# ShieldValvesSensor-v0.net
KiCad netlist of a schematic drawn in EAGLE
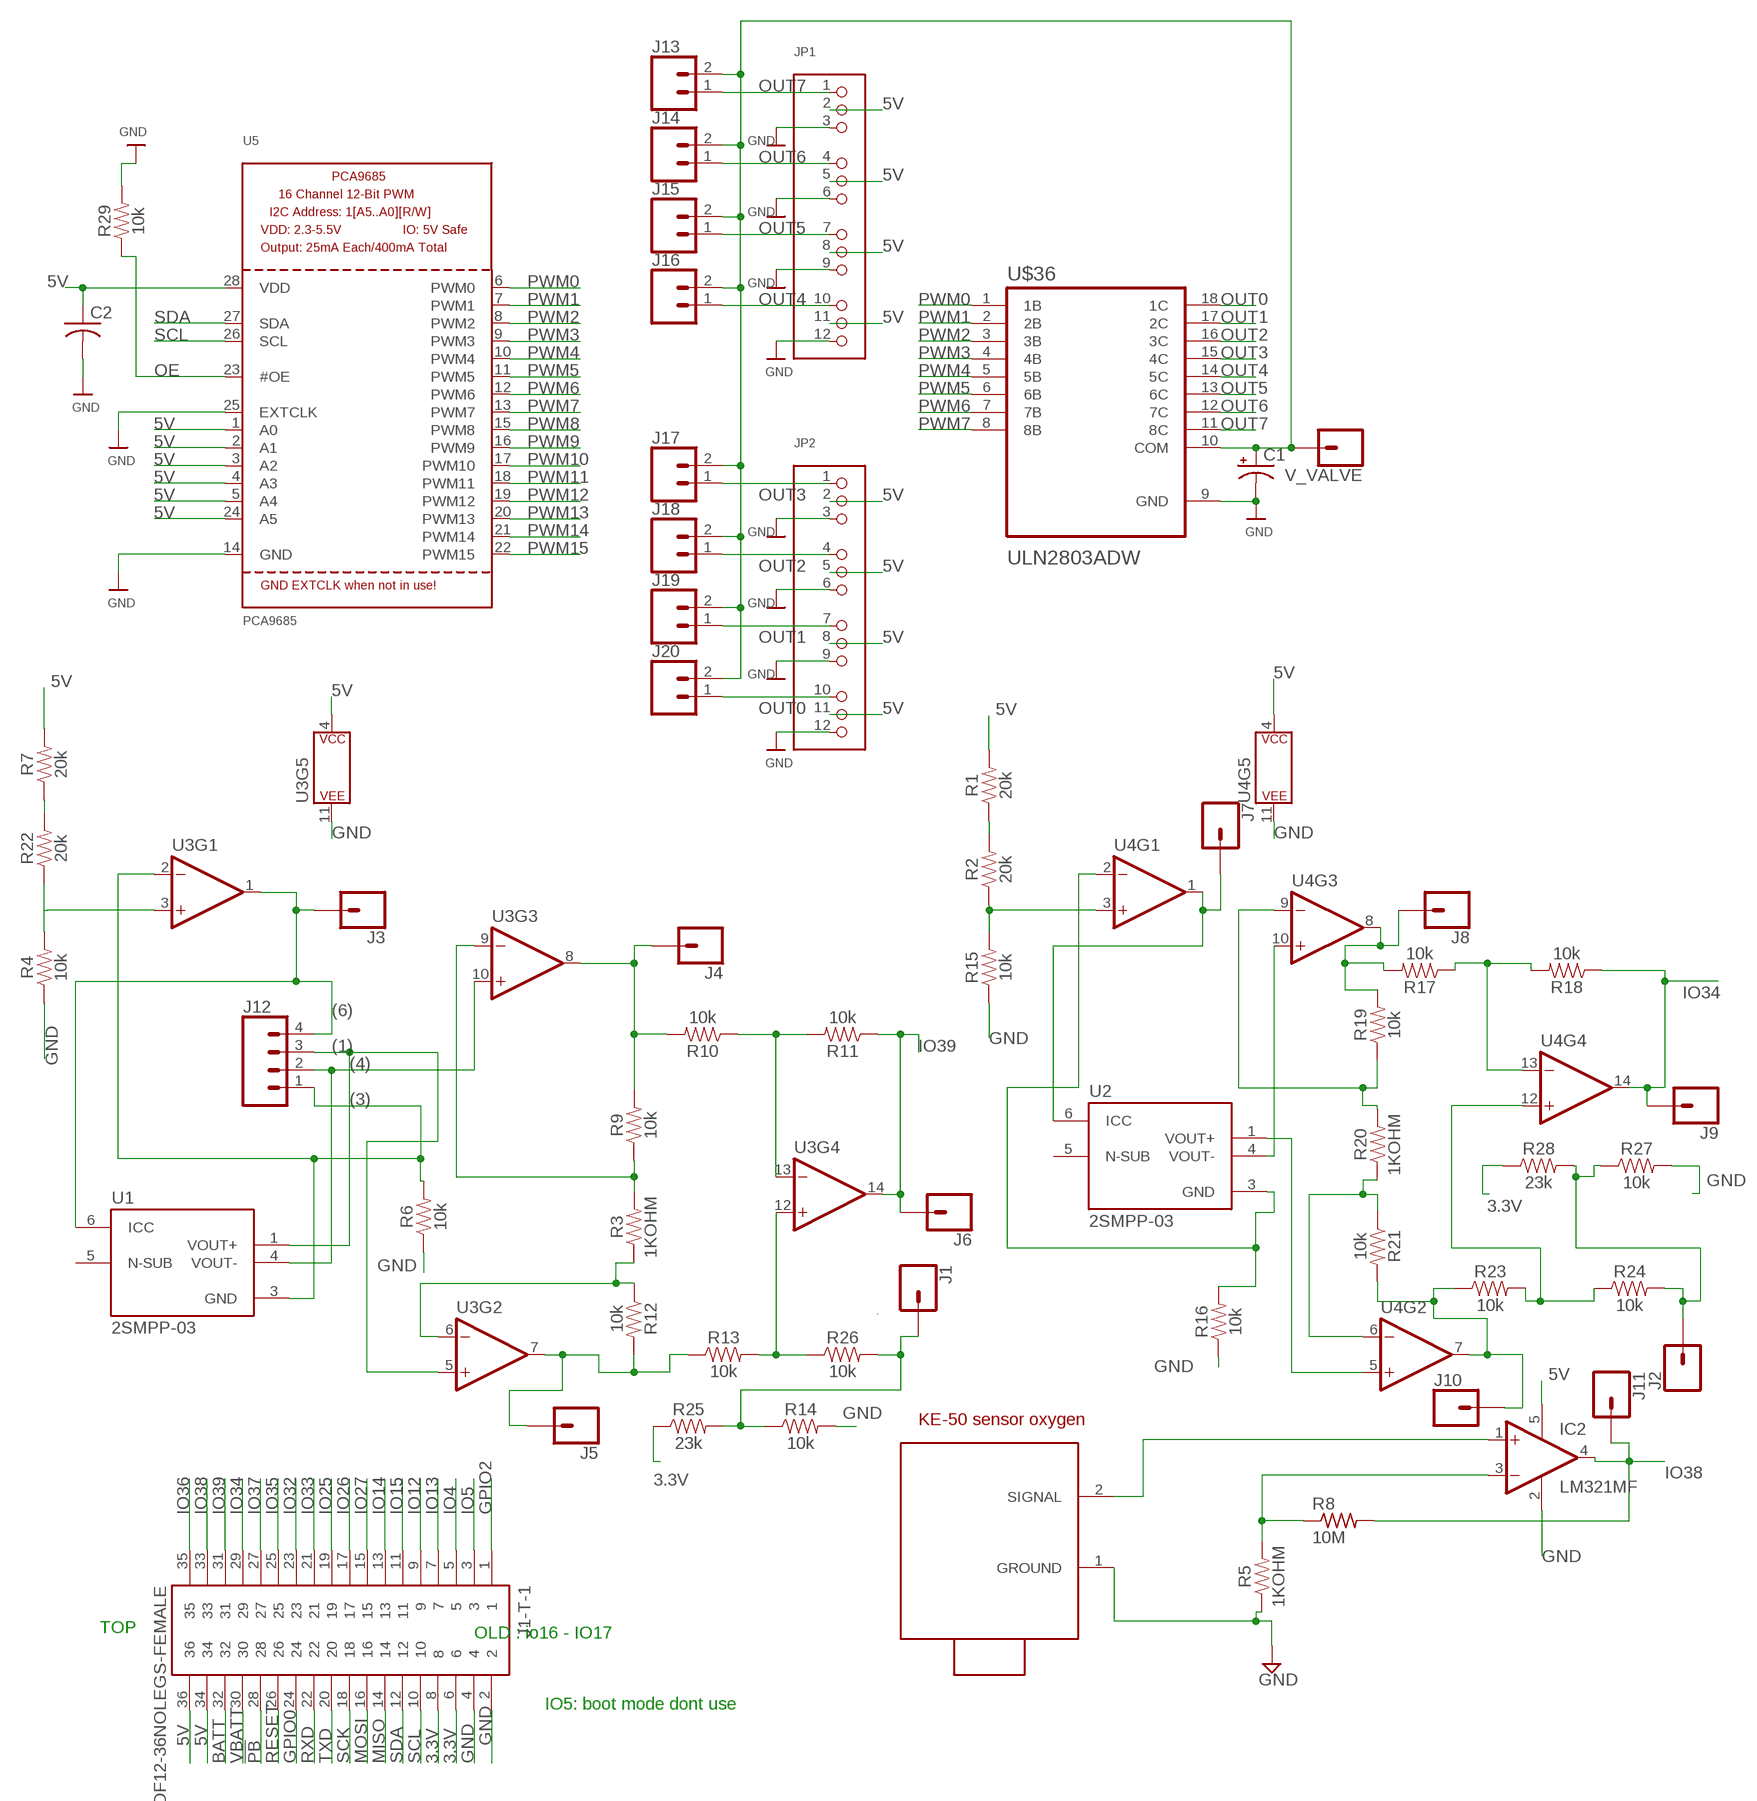
[diagram p0: schematic, sheet 1]

(export (version "E")
  (design (tool "Eeschema 10.0.6"))
  (components
    (comp (ref "C1")
      (value "CPOL-USE2-4")
      (footprint "eagle-import:E2-4")
      (libsource (lib "eagle-import") (part "CPOL-USE2-4"))
    )
    (comp (ref "C2")
      (value "C-USC0402")
      (footprint "eagle-import:C0402")
      (libsource (lib "eagle-import") (part "C-USC0402"))
    )
    (comp (ref "IC2")
      (value "LM321MF")
      (footprint "eagle-import:SOT23-5")
      (libsource (lib "eagle-import") (part "LM321?MF"))
    )
    (comp (ref "J1")
      (value "CONN_01")
      (footprint "eagle-import:1X01")
      (libsource (lib "eagle-import") (part "CONN_01"))
    )
    (comp (ref "J1-T-1")
      (value "DF12-36NOLEGS-FEMALE")
      (footprint "eagle-import:DF12-36-DP-NL")
      (libsource (lib "eagle-import") (part "DF12-36NOLEGS-FEMALE"))
    )
    (comp (ref "J2")
      (value "CONN_01")
      (footprint "eagle-import:1X01")
      (libsource (lib "eagle-import") (part "CONN_01"))
    )
    (comp (ref "J3")
      (value "CONN_01")
      (footprint "eagle-import:1X01")
      (libsource (lib "eagle-import") (part "CONN_01"))
    )
    (comp (ref "J4")
      (value "CONN_01")
      (footprint "eagle-import:1X01")
      (libsource (lib "eagle-import") (part "CONN_01"))
    )
    (comp (ref "J5")
      (value "CONN_01")
      (footprint "eagle-import:1X01")
      (libsource (lib "eagle-import") (part "CONN_01"))
    )
    (comp (ref "J6")
      (value "CONN_01")
      (footprint "eagle-import:1X01")
      (libsource (lib "eagle-import") (part "CONN_01"))
    )
    (comp (ref "J7")
      (value "CONN_01")
      (footprint "eagle-import:1X01")
      (libsource (lib "eagle-import") (part "CONN_01"))
    )
    (comp (ref "J8")
      (value "CONN_01")
      (footprint "eagle-import:1X01")
      (libsource (lib "eagle-import") (part "CONN_01"))
    )
    (comp (ref "J9")
      (value "CONN_01")
      (footprint "eagle-import:1X01")
      (libsource (lib "eagle-import") (part "CONN_01"))
    )
    (comp (ref "J10")
      (value "CONN_01")
      (footprint "eagle-import:1X01")
      (libsource (lib "eagle-import") (part "CONN_01"))
    )
    (comp (ref "J11")
      (value "CONN_01")
      (footprint "eagle-import:1X01")
      (libsource (lib "eagle-import") (part "CONN_01"))
    )
    (comp (ref "J12")
      (value "CONN_04PTH")
      (footprint "eagle-import:1X04")
      (libsource (lib "eagle-import") (part "CONN_04PTH"))
    )
    (comp (ref "J13")
      (value "CONN_02")
      (footprint "eagle-import:1X02")
      (libsource (lib "eagle-import") (part "CONN_02"))
    )
    (comp (ref "J14")
      (value "CONN_02")
      (footprint "eagle-import:1X02")
      (libsource (lib "eagle-import") (part "CONN_02"))
    )
    (comp (ref "J15")
      (value "CONN_02")
      (footprint "eagle-import:1X02")
      (libsource (lib "eagle-import") (part "CONN_02"))
    )
    (comp (ref "J16")
      (value "CONN_02")
      (footprint "eagle-import:1X02")
      (libsource (lib "eagle-import") (part "CONN_02"))
    )
    (comp (ref "J17")
      (value "CONN_02")
      (footprint "eagle-import:1X02")
      (libsource (lib "eagle-import") (part "CONN_02"))
    )
    (comp (ref "J18")
      (value "CONN_02")
      (footprint "eagle-import:1X02")
      (libsource (lib "eagle-import") (part "CONN_02"))
    )
    (comp (ref "J19")
      (value "CONN_02")
      (footprint "eagle-import:1X02")
      (libsource (lib "eagle-import") (part "CONN_02"))
    )
    (comp (ref "J20")
      (value "CONN_02")
      (footprint "eagle-import:1X02")
      (libsource (lib "eagle-import") (part "CONN_02"))
    )
    (comp (ref "JP1")
      (value "HEADER-3X04")
      (footprint "eagle-import:3X04")
      (libsource (lib "eagle-import") (part "HEADER-3X04"))
    )
    (comp (ref "JP2")
      (value "HEADER-3X04")
      (footprint "eagle-import:3X04")
      (libsource (lib "eagle-import") (part "HEADER-3X04"))
    )
    (comp (ref "R1")
      (value "20k")
      (footprint "eagle-import:0402-TIGHT")
      (libsource (lib "eagle-import") (part "20KOHM-0402T-1/16W-1%"))
    )
    (comp (ref "R2")
      (value "20k")
      (footprint "eagle-import:0402-TIGHT")
      (libsource (lib "eagle-import") (part "20KOHM-0402T-1/16W-1%"))
    )
    (comp (ref "R3")
      (value "1KOHM")
      (footprint "eagle-import:0402")
      (libsource (lib "eagle-import") (part "1KOHM-0402-1/16W-1%"))
    )
    (comp (ref "R4")
      (value "10k")
      (footprint "eagle-import:0402")
      (libsource (lib "eagle-import") (part "10KOHM-0402-1/16W-1%"))
    )
    (comp (ref "R5")
      (value "1KOHM")
      (footprint "eagle-import:0402")
      (libsource (lib "eagle-import") (part "1KOHM-0402-1/16W-1%"))
    )
    (comp (ref "R6")
      (value "10k")
      (footprint "eagle-import:0402")
      (libsource (lib "eagle-import") (part "10KOHM-0402-1/16W-1%"))
    )
    (comp (ref "R7")
      (value "20k")
      (footprint "eagle-import:0402-TIGHT")
      (libsource (lib "eagle-import") (part "20KOHM-0402T-1/16W-1%"))
    )
    (comp (ref "R8")
      (value "10M")
      (footprint "eagle-import:R0402")
      (libsource (lib "eagle-import") (part "R-US_R0402"))
    )
    (comp (ref "R9")
      (value "10k")
      (footprint "eagle-import:0402")
      (libsource (lib "eagle-import") (part "10KOHM-0402-1/16W-1%"))
    )
    (comp (ref "R10")
      (value "10k")
      (footprint "eagle-import:0402")
      (libsource (lib "eagle-import") (part "10KOHM-0402-1/16W-1%"))
    )
    (comp (ref "R11")
      (value "10k")
      (footprint "eagle-import:0402")
      (libsource (lib "eagle-import") (part "10KOHM-0402-1/16W-1%"))
    )
    (comp (ref "R12")
      (value "10k")
      (footprint "eagle-import:0402")
      (libsource (lib "eagle-import") (part "10KOHM-0402-1/16W-1%"))
    )
    (comp (ref "R13")
      (value "10k")
      (footprint "eagle-import:0402")
      (libsource (lib "eagle-import") (part "10KOHM-0402-1/16W-1%"))
    )
    (comp (ref "R14")
      (value "10k")
      (footprint "eagle-import:0402")
      (libsource (lib "eagle-import") (part "10KOHM-0402-1/16W-1%"))
    )
    (comp (ref "R15")
      (value "10k")
      (footprint "eagle-import:0402")
      (libsource (lib "eagle-import") (part "10KOHM-0402-1/16W-1%"))
    )
    (comp (ref "R16")
      (value "10k")
      (footprint "eagle-import:0402")
      (libsource (lib "eagle-import") (part "10KOHM-0402-1/16W-1%"))
    )
    (comp (ref "R17")
      (value "10k")
      (footprint "eagle-import:0402")
      (libsource (lib "eagle-import") (part "10KOHM-0402-1/16W-1%"))
    )
    (comp (ref "R18")
      (value "10k")
      (footprint "eagle-import:0402")
      (libsource (lib "eagle-import") (part "10KOHM-0402-1/16W-1%"))
    )
    (comp (ref "R19")
      (value "10k")
      (footprint "eagle-import:0402")
      (libsource (lib "eagle-import") (part "10KOHM-0402-1/16W-1%"))
    )
    (comp (ref "R20")
      (value "1KOHM")
      (footprint "eagle-import:0402")
      (libsource (lib "eagle-import") (part "1KOHM-0402-1/16W-1%"))
    )
    (comp (ref "R21")
      (value "10k")
      (footprint "eagle-import:0402")
      (libsource (lib "eagle-import") (part "10KOHM-0402-1/16W-1%"))
    )
    (comp (ref "R22")
      (value "20k")
      (footprint "eagle-import:0402-TIGHT")
      (libsource (lib "eagle-import") (part "20KOHM-0402T-1/16W-1%"))
    )
    (comp (ref "R23")
      (value "10k")
      (footprint "eagle-import:0402")
      (libsource (lib "eagle-import") (part "10KOHM-0402-1/16W-1%"))
    )
    (comp (ref "R24")
      (value "10k")
      (footprint "eagle-import:0402")
      (libsource (lib "eagle-import") (part "10KOHM-0402-1/16W-1%"))
    )
    (comp (ref "R25")
      (value "23k")
      (footprint "eagle-import:0402-TIGHT")
      (libsource (lib "eagle-import") (part "22KOHM-0402_TIGHT-1/10W-1%"))
    )
    (comp (ref "R26")
      (value "10k")
      (footprint "eagle-import:0402")
      (libsource (lib "eagle-import") (part "10KOHM-0402-1/16W-1%"))
    )
    (comp (ref "R27")
      (value "10k")
      (footprint "eagle-import:0402")
      (libsource (lib "eagle-import") (part "10KOHM-0402-1/16W-1%"))
    )
    (comp (ref "R28")
      (value "23k")
      (footprint "eagle-import:0402-TIGHT")
      (libsource (lib "eagle-import") (part "22KOHM-0402_TIGHT-1/10W-1%"))
    )
    (comp (ref "R29")
      (value "10k")
      (footprint "eagle-import:0402")
      (libsource (lib "eagle-import") (part "10KOHM-0402-1/16W-1%"))
    )
    (comp (ref "U$5")
      (value "KE-50")
      (footprint "eagle-import:KE")
      (libsource (lib "eagle-import") (part "KE-50"))
    )
    (comp (ref "U$36")
      (value "ULN2803ADW")
      (footprint "eagle-import:SOIC127P1030X265-18N")
      (libsource (lib "eagle-import") (part "ULN2803ADW"))
    )
    (comp (ref "U1")
      (value "2SMPP-03")
      (footprint "eagle-import:XDCR_2SMPP-03")
      (fields (field (name "MF") "Omron Electronics"))
      (libsource (lib "eagle-import") (part "2SMPP-03"))
    )
    (comp (ref "U2")
      (value "2SMPP-03")
      (footprint "eagle-import:XDCR_2SMPP-03")
      (fields (field (name "MF") "Omron Electronics"))
      (libsource (lib "eagle-import") (part "2SMPP-03"))
    )
    (comp (ref "U3")
      (value "LMV324SOP127P780X200-14N")
      (footprint "eagle-import:SOP127P780X200-14N")
      (libsource (lib "eagle-import") (part "LMV324SOP127P780X200-14N"))
    )
    (comp (ref "U4")
      (value "LMV324SOP127P780X200-14N")
      (footprint "eagle-import:SOP127P780X200-14N")
      (libsource (lib "eagle-import") (part "LMV324SOP127P780X200-14N"))
    )
    (comp (ref "U5")
      (value "PCA9685")
      (footprint "eagle-import:TSSOP28")
      (libsource (lib "eagle-import") (part "PCA9685"))
    )
    (comp (ref "V_VALVE")
      (value "CONN_01")
      (footprint "eagle-import:1X01")
      (libsource (lib "eagle-import") (part "SparkFun-Connectors_513_CONN_01"))
    )
  )
  (nets
    (net (code "1") (name "/(1)") (class "Default")
      (node (ref "J12") (pin "3") (pinfunction "3_3") (pintype "passive"))
      (node (ref "U1") (pin "1") (pinfunction "VOUT+_1") (pintype "output"))
      (node (ref "U3") (pin "5") (pinfunction "+IN_5") (pintype "input"))
    )
    (net (code "2") (name "/(3)") (class "Default")
      (node (ref "J12") (pin "1") (pinfunction "1_1") (pintype "passive"))
      (node (ref "R6") (pin "2") (pinfunction "2_2") (pintype "passive"))
      (node (ref "U1") (pin "3") (pinfunction "GND_3") (pintype "power_in"))
      (node (ref "U3") (pin "2") (pinfunction "-IN_2") (pintype "input"))
    )
    (net (code "3") (name "/(4)") (class "Default")
      (node (ref "J12") (pin "2") (pinfunction "2_2") (pintype "passive"))
      (node (ref "U1") (pin "4") (pinfunction "VOUT-_4") (pintype "output"))
      (node (ref "U3") (pin "10") (pinfunction "+IN_10") (pintype "input"))
    )
    (net (code "4") (name "/(6)") (class "Default")
      (node (ref "J12") (pin "4") (pinfunction "4_4") (pintype "passive"))
      (node (ref "J3") (pin "1") (pinfunction "1_1") (pintype "passive"))
      (node (ref "U1") (pin "6") (pinfunction "ICC_6") (pintype "input"))
      (node (ref "U3") (pin "1") (pinfunction "OUT_1") (pintype "output"))
    )
    (net (code "5") (name "/3.3V") (class "Default")
      (node (ref "J1-T-1") (pin "6") (pinfunction "6_6") (pintype "bidirectional"))
      (node (ref "J1-T-1") (pin "8") (pinfunction "8_8") (pintype "bidirectional"))
      (node (ref "R25") (pin "1") (pinfunction "1_1") (pintype "passive"))
      (node (ref "R28") (pin "1") (pinfunction "1_1") (pintype "passive"))
    )
    (net (code "6") (name "/5V") (class "Default")
      (node (ref "C2") (pin "1") (pinfunction "1_1") (pintype "passive"))
      (node (ref "IC2") (pin "5") (pinfunction "V+_5") (pintype "power_in"))
      (node (ref "J1-T-1") (pin "34") (pinfunction "34_34") (pintype "bidirectional"))
      (node (ref "J1-T-1") (pin "36") (pinfunction "36_36") (pintype "bidirectional"))
      (node (ref "JP1") (pin "11") (pinfunction "11_11") (pintype "passive"))
      (node (ref "JP1") (pin "2") (pinfunction "2_2") (pintype "passive"))
      (node (ref "JP1") (pin "5") (pinfunction "5_5") (pintype "passive"))
      (node (ref "JP1") (pin "8") (pinfunction "8_8") (pintype "passive"))
      (node (ref "JP2") (pin "11") (pinfunction "11_11") (pintype "passive"))
      (node (ref "JP2") (pin "2") (pinfunction "2_2") (pintype "passive"))
      (node (ref "JP2") (pin "5") (pinfunction "5_5") (pintype "passive"))
      (node (ref "JP2") (pin "8") (pinfunction "8_8") (pintype "passive"))
      (node (ref "R1") (pin "2") (pinfunction "2_2") (pintype "passive"))
      (node (ref "R7") (pin "2") (pinfunction "2_2") (pintype "passive"))
      (node (ref "U3") (pin "4") (pinfunction "P$V+_4") (pintype "bidirectional"))
      (node (ref "U4") (pin "4") (pinfunction "P$V+_4") (pintype "bidirectional"))
      (node (ref "U5") (pin "1") (pinfunction "A0_1") (pintype "bidirectional"))
      (node (ref "U5") (pin "2") (pinfunction "A1_2") (pintype "bidirectional"))
      (node (ref "U5") (pin "24") (pinfunction "A5_24") (pintype "bidirectional"))
      (node (ref "U5") (pin "28") (pinfunction "VDD_28") (pintype "power_in"))
      (node (ref "U5") (pin "3") (pinfunction "A2_3") (pintype "bidirectional"))
      (node (ref "U5") (pin "4") (pinfunction "A3_4") (pintype "bidirectional"))
      (node (ref "U5") (pin "5") (pinfunction "A4_5") (pintype "bidirectional"))
    )
    (net (code "7") (name "/BATT") (class "Default")
      (node (ref "J1-T-1") (pin "32") (pinfunction "32_32") (pintype "bidirectional"))
    )
    (net (code "8") (name "/GPIO0") (class "Default")
      (node (ref "J1-T-1") (pin "24") (pinfunction "24_24") (pintype "bidirectional"))
    )
    (net (code "9") (name "/GPIO2") (class "Default")
      (node (ref "J1-T-1") (pin "1") (pinfunction "1_1") (pintype "bidirectional"))
    )
    (net (code "10") (name "/IO4") (class "Default")
      (node (ref "J1-T-1") (pin "5") (pinfunction "5_5") (pintype "bidirectional"))
    )
    (net (code "11") (name "/IO5") (class "Default")
      (node (ref "J1-T-1") (pin "3") (pinfunction "3_3") (pintype "bidirectional"))
    )
    (net (code "12") (name "/IO12") (class "Default")
      (node (ref "J1-T-1") (pin "9") (pinfunction "9_9") (pintype "bidirectional"))
    )
    (net (code "13") (name "/IO13") (class "Default")
      (node (ref "J1-T-1") (pin "7") (pinfunction "7_7") (pintype "bidirectional"))
    )
    (net (code "14") (name "/IO14") (class "Default")
      (node (ref "J1-T-1") (pin "13") (pinfunction "13_13") (pintype "bidirectional"))
    )
    (net (code "15") (name "/IO15") (class "Default")
      (node (ref "J1-T-1") (pin "11") (pinfunction "11_11") (pintype "bidirectional"))
    )
    (net (code "16") (name "/IO25") (class "Default")
      (node (ref "J1-T-1") (pin "19") (pinfunction "19_19") (pintype "bidirectional"))
    )
    (net (code "17") (name "/IO26") (class "Default")
      (node (ref "J1-T-1") (pin "17") (pinfunction "17_17") (pintype "bidirectional"))
    )
    (net (code "18") (name "/IO27") (class "Default")
      (node (ref "J1-T-1") (pin "15") (pinfunction "15_15") (pintype "bidirectional"))
    )
    (net (code "19") (name "/IO32") (class "Default")
      (node (ref "J1-T-1") (pin "23") (pinfunction "23_23") (pintype "bidirectional"))
    )
    (net (code "20") (name "/IO33") (class "Default")
      (node (ref "J1-T-1") (pin "21") (pinfunction "21_21") (pintype "bidirectional"))
    )
    (net (code "21") (name "/IO34") (class "Default")
      (node (ref "J1-T-1") (pin "29") (pinfunction "29_29") (pintype "bidirectional"))
      (node (ref "J9") (pin "1") (pinfunction "1_1") (pintype "passive"))
      (node (ref "R18") (pin "1") (pinfunction "1_1") (pintype "passive"))
      (node (ref "U4") (pin "14") (pinfunction "OUT_14") (pintype "output"))
    )
    (net (code "22") (name "/IO35") (class "Default")
      (node (ref "J1-T-1") (pin "25") (pinfunction "25_25") (pintype "bidirectional"))
    )
    (net (code "23") (name "/IO36") (class "Default")
      (node (ref "J1-T-1") (pin "35") (pinfunction "35_35") (pintype "bidirectional"))
    )
    (net (code "24") (name "/IO37") (class "Default")
      (node (ref "J1-T-1") (pin "27") (pinfunction "27_27") (pintype "bidirectional"))
    )
    (net (code "25") (name "/IO38") (class "Default")
      (node (ref "IC2") (pin "4") (pinfunction "OUT_4") (pintype "output"))
      (node (ref "J1-T-1") (pin "33") (pinfunction "33_33") (pintype "bidirectional"))
      (node (ref "J11") (pin "1") (pinfunction "1_1") (pintype "passive"))
      (node (ref "R8") (pin "2") (pinfunction "2_2") (pintype "passive"))
    )
    (net (code "26") (name "/IO39") (class "Default")
      (node (ref "J1-T-1") (pin "31") (pinfunction "31_31") (pintype "bidirectional"))
      (node (ref "J6") (pin "1") (pinfunction "1_1") (pintype "passive"))
      (node (ref "R11") (pin "1") (pinfunction "1_1") (pintype "passive"))
      (node (ref "U3") (pin "14") (pinfunction "OUT_14") (pintype "output"))
    )
    (net (code "27") (name "/MISO") (class "Default")
      (node (ref "J1-T-1") (pin "14") (pinfunction "14_14") (pintype "bidirectional"))
    )
    (net (code "28") (name "/MOSI") (class "Default")
      (node (ref "J1-T-1") (pin "16") (pinfunction "16_16") (pintype "bidirectional"))
    )
    (net (code "29") (name "/OE") (class "Default")
      (node (ref "R29") (pin "1") (pinfunction "1_1") (pintype "passive"))
      (node (ref "U5") (pin "23") (pinfunction "#OE_23") (pintype "input"))
    )
    (net (code "30") (name "/OUT0") (class "Default")
      (node (ref "J20") (pin "1") (pinfunction "1_1") (pintype "passive"))
      (node (ref "JP2") (pin "10") (pinfunction "10_10") (pintype "passive"))
      (node (ref "U$36") (pin "18") (pinfunction "1C_18") (pintype "output"))
    )
    (net (code "31") (name "/OUT1") (class "Default")
      (node (ref "J19") (pin "1") (pinfunction "1_1") (pintype "passive"))
      (node (ref "JP2") (pin "7") (pinfunction "7_7") (pintype "passive"))
      (node (ref "U$36") (pin "17") (pinfunction "2C_17") (pintype "output"))
    )
    (net (code "32") (name "/OUT2") (class "Default")
      (node (ref "J18") (pin "1") (pinfunction "1_1") (pintype "passive"))
      (node (ref "JP2") (pin "4") (pinfunction "4_4") (pintype "passive"))
      (node (ref "U$36") (pin "16") (pinfunction "3C_16") (pintype "output"))
    )
    (net (code "33") (name "/OUT3") (class "Default")
      (node (ref "J17") (pin "1") (pinfunction "1_1") (pintype "passive"))
      (node (ref "JP2") (pin "1") (pinfunction "1_1") (pintype "passive"))
      (node (ref "U$36") (pin "15") (pinfunction "4C_15") (pintype "output"))
    )
    (net (code "34") (name "/OUT4") (class "Default")
      (node (ref "J16") (pin "1") (pinfunction "1_1") (pintype "passive"))
      (node (ref "JP1") (pin "10") (pinfunction "10_10") (pintype "passive"))
      (node (ref "U$36") (pin "14") (pinfunction "5C_14") (pintype "output"))
    )
    (net (code "35") (name "/OUT5") (class "Default")
      (node (ref "J15") (pin "1") (pinfunction "1_1") (pintype "passive"))
      (node (ref "JP1") (pin "7") (pinfunction "7_7") (pintype "passive"))
      (node (ref "U$36") (pin "13") (pinfunction "6C_13") (pintype "output"))
    )
    (net (code "36") (name "/OUT6") (class "Default")
      (node (ref "J14") (pin "1") (pinfunction "1_1") (pintype "passive"))
      (node (ref "JP1") (pin "4") (pinfunction "4_4") (pintype "passive"))
      (node (ref "U$36") (pin "12") (pinfunction "7C_12") (pintype "output"))
    )
    (net (code "37") (name "/OUT7") (class "Default")
      (node (ref "J13") (pin "1") (pinfunction "1_1") (pintype "passive"))
      (node (ref "JP1") (pin "1") (pinfunction "1_1") (pintype "passive"))
      (node (ref "U$36") (pin "11") (pinfunction "8C_11") (pintype "output"))
    )
    (net (code "38") (name "/PWM0") (class "Default")
      (node (ref "U$36") (pin "1") (pinfunction "1B_1") (pintype "input"))
      (node (ref "U5") (pin "6") (pinfunction "PWM0_6") (pintype "output"))
    )
    (net (code "39") (name "/PWM1") (class "Default")
      (node (ref "U$36") (pin "2") (pinfunction "2B_2") (pintype "input"))
      (node (ref "U5") (pin "7") (pinfunction "PWM1_7") (pintype "output"))
    )
    (net (code "40") (name "/PWM2") (class "Default")
      (node (ref "U$36") (pin "3") (pinfunction "3B_3") (pintype "input"))
      (node (ref "U5") (pin "8") (pinfunction "PWM2_8") (pintype "output"))
    )
    (net (code "41") (name "/PWM3") (class "Default")
      (node (ref "U$36") (pin "4") (pinfunction "4B_4") (pintype "input"))
      (node (ref "U5") (pin "9") (pinfunction "PWM3_9") (pintype "output"))
    )
    (net (code "42") (name "/PWM4") (class "Default")
      (node (ref "U$36") (pin "5") (pinfunction "5B_5") (pintype "input"))
      (node (ref "U5") (pin "10") (pinfunction "PWM4_10") (pintype "output"))
    )
    (net (code "43") (name "/PWM5") (class "Default")
      (node (ref "U$36") (pin "6") (pinfunction "6B_6") (pintype "input"))
      (node (ref "U5") (pin "11") (pinfunction "PWM5_11") (pintype "output"))
    )
    (net (code "44") (name "/PWM6") (class "Default")
      (node (ref "U$36") (pin "7") (pinfunction "7B_7") (pintype "input"))
      (node (ref "U5") (pin "12") (pinfunction "PWM6_12") (pintype "output"))
    )
    (net (code "45") (name "/PWM7") (class "Default")
      (node (ref "U$36") (pin "8") (pinfunction "8B_8") (pintype "input"))
      (node (ref "U5") (pin "13") (pinfunction "PWM7_13") (pintype "output"))
    )
    (net (code "46") (name "/PWM8") (class "Default")
      (node (ref "U5") (pin "15") (pinfunction "PWM8_15") (pintype "output"))
    )
    (net (code "47") (name "/PWM9") (class "Default")
      (node (ref "U5") (pin "16") (pinfunction "PWM9_16") (pintype "output"))
    )
    (net (code "48") (name "/PWM10") (class "Default")
      (node (ref "U5") (pin "17") (pinfunction "PWM10_17") (pintype "output"))
    )
    (net (code "49") (name "/PWM11") (class "Default")
      (node (ref "U5") (pin "18") (pinfunction "PWM11_18") (pintype "output"))
    )
    (net (code "50") (name "/PWM12") (class "Default")
      (node (ref "U5") (pin "19") (pinfunction "PWM12_19") (pintype "output"))
    )
    (net (code "51") (name "/PWM13") (class "Default")
      (node (ref "U5") (pin "20") (pinfunction "PWM13_20") (pintype "output"))
    )
    (net (code "52") (name "/PWM14") (class "Default")
      (node (ref "U5") (pin "21") (pinfunction "PWM14_21") (pintype "output"))
    )
    (net (code "53") (name "/PWM15") (class "Default")
      (node (ref "U5") (pin "22") (pinfunction "PWM15_22") (pintype "output"))
    )
    (net (code "54") (name "/RESET") (class "Default")
      (node (ref "J1-T-1") (pin "26") (pinfunction "26_26") (pintype "bidirectional"))
    )
    (net (code "55") (name "/RXD") (class "Default")
      (node (ref "J1-T-1") (pin "22") (pinfunction "22_22") (pintype "bidirectional"))
    )
    (net (code "56") (name "/SCK") (class "Default")
      (node (ref "J1-T-1") (pin "18") (pinfunction "18_18") (pintype "bidirectional"))
    )
    (net (code "57") (name "/SCL") (class "Default")
      (node (ref "J1-T-1") (pin "10") (pinfunction "10_10") (pintype "bidirectional"))
      (node (ref "U5") (pin "26") (pinfunction "SCL_26") (pintype "bidirectional"))
    )
    (net (code "58") (name "/SDA") (class "Default")
      (node (ref "J1-T-1") (pin "12") (pinfunction "12_12") (pintype "bidirectional"))
      (node (ref "U5") (pin "27") (pinfunction "SDA_27") (pintype "bidirectional"))
    )
    (net (code "59") (name "/TXD") (class "Default")
      (node (ref "J1-T-1") (pin "20") (pinfunction "20_20") (pintype "bidirectional"))
    )
    (net (code "60") (name "/VBATT") (class "Default")
      (node (ref "J1-T-1") (pin "30") (pinfunction "30_30") (pintype "bidirectional"))
    )
    (net (code "61") (name "/~{PB}") (class "Default")
      (node (ref "J1-T-1") (pin "28") (pinfunction "28_28") (pintype "bidirectional"))
    )
    (net (code "62") (name "GND") (class "Default")
      (node (ref "C1") (pin "-") (pinfunction "-_-") (pintype "passive"))
      (node (ref "C2") (pin "2") (pinfunction "2_2") (pintype "passive"))
      (node (ref "IC2") (pin "2") (pinfunction "V-_2") (pintype "power_in"))
      (node (ref "J1-T-1") (pin "2") (pinfunction "2_2") (pintype "bidirectional"))
      (node (ref "J1-T-1") (pin "4") (pinfunction "4_4") (pintype "bidirectional"))
      (node (ref "JP1") (pin "12") (pinfunction "12_12") (pintype "passive"))
      (node (ref "JP1") (pin "3") (pinfunction "3_3") (pintype "passive"))
      (node (ref "JP1") (pin "6") (pinfunction "6_6") (pintype "passive"))
      (node (ref "JP1") (pin "9") (pinfunction "9_9") (pintype "passive"))
      (node (ref "JP2") (pin "12") (pinfunction "12_12") (pintype "passive"))
      (node (ref "JP2") (pin "3") (pinfunction "3_3") (pintype "passive"))
      (node (ref "JP2") (pin "6") (pinfunction "6_6") (pintype "passive"))
      (node (ref "JP2") (pin "9") (pinfunction "9_9") (pintype "passive"))
      (node (ref "R14") (pin "2") (pinfunction "2_2") (pintype "passive"))
      (node (ref "R15") (pin "1") (pinfunction "1_1") (pintype "passive"))
      (node (ref "R16") (pin "1") (pinfunction "1_1") (pintype "passive"))
      (node (ref "R27") (pin "2") (pinfunction "2_2") (pintype "passive"))
      (node (ref "R29") (pin "2") (pinfunction "2_2") (pintype "passive"))
      (node (ref "R4") (pin "1") (pinfunction "1_1") (pintype "passive"))
      (node (ref "R5") (pin "1") (pinfunction "1_1") (pintype "passive"))
      (node (ref "R6") (pin "1") (pinfunction "1_1") (pintype "passive"))
      (node (ref "U$36") (pin "9") (pinfunction "GND_9") (pintype "power_in"))
      (node (ref "U$5") (pin "1") (pinfunction "GROUND_1") (pintype "bidirectional"))
      (node (ref "U3") (pin "11") (pinfunction "P$V-_11") (pintype "bidirectional"))
      (node (ref "U4") (pin "11") (pinfunction "P$V-_11") (pintype "bidirectional"))
      (node (ref "U5") (pin "14") (pinfunction "GND_14") (pintype "power_in"))
      (node (ref "U5") (pin "25") (pinfunction "EXTCLK_25") (pintype "input"))
    )
    (net (code "63") (name "Net-(IC2-+IN)") (class "Default")
      (node (ref "IC2") (pin "1") (pinfunction "+IN_1") (pintype "input"))
      (node (ref "U$5") (pin "2") (pinfunction "SIGNAL_2") (pintype "bidirectional"))
    )
    (net (code "64") (name "Net-(IC2--IN)") (class "Default")
      (node (ref "IC2") (pin "3") (pinfunction "-IN_3") (pintype "input"))
      (node (ref "R5") (pin "2") (pinfunction "2_2") (pintype "passive"))
      (node (ref "R8") (pin "1") (pinfunction "1_1") (pintype "passive"))
    )
    (net (code "65") (name "Net-(J1-Pad1)") (class "Default")
      (node (ref "J1") (pin "1") (pinfunction "1_1") (pintype "passive"))
      (node (ref "R14") (pin "1") (pinfunction "1_1") (pintype "passive"))
      (node (ref "R25") (pin "2") (pinfunction "2_2") (pintype "passive"))
      (node (ref "R26") (pin "2") (pinfunction "2_2") (pintype "passive"))
    )
    (net (code "66") (name "Net-(J2-Pad1)") (class "Default")
      (node (ref "J2") (pin "1") (pinfunction "1_1") (pintype "passive"))
      (node (ref "R24") (pin "2") (pinfunction "2_2") (pintype "passive"))
      (node (ref "R27") (pin "1") (pinfunction "1_1") (pintype "passive"))
      (node (ref "R28") (pin "2") (pinfunction "2_2") (pintype "passive"))
    )
    (net (code "67") (name "Net-(R1-Pad1)") (class "Default")
      (node (ref "R1") (pin "1") (pinfunction "1_1") (pintype "passive"))
      (node (ref "R2") (pin "2") (pinfunction "2_2") (pintype "passive"))
    )
    (net (code "68") (name "Net-(R10-Pad1)") (class "Default")
      (node (ref "R10") (pin "1") (pinfunction "1_1") (pintype "passive"))
      (node (ref "R11") (pin "2") (pinfunction "2_2") (pintype "passive"))
    )
    (net (code "69") (name "Net-(R15-Pad2)") (class "Default")
      (node (ref "R15") (pin "2") (pinfunction "2_2") (pintype "passive"))
      (node (ref "R2") (pin "1") (pinfunction "1_1") (pintype "passive"))
    )
    (net (code "70") (name "Net-(R22-Pad2)") (class "Default")
      (node (ref "R22") (pin "2") (pinfunction "2_2") (pintype "passive"))
      (node (ref "R7") (pin "1") (pinfunction "1_1") (pintype "passive"))
    )
    (net (code "71") (name "Net-(U$36-COM)") (class "Default")
      (node (ref "C1") (pin "+") (pinfunction "+_+") (pintype "passive"))
      (node (ref "J13") (pin "2") (pinfunction "2_2") (pintype "passive"))
      (node (ref "J14") (pin "2") (pinfunction "2_2") (pintype "passive"))
      (node (ref "J15") (pin "2") (pinfunction "2_2") (pintype "passive"))
      (node (ref "J16") (pin "2") (pinfunction "2_2") (pintype "passive"))
      (node (ref "J17") (pin "2") (pinfunction "2_2") (pintype "passive"))
      (node (ref "J18") (pin "2") (pinfunction "2_2") (pintype "passive"))
      (node (ref "J19") (pin "2") (pinfunction "2_2") (pintype "passive"))
      (node (ref "J20") (pin "2") (pinfunction "2_2") (pintype "passive"))
      (node (ref "U$36") (pin "10") (pinfunction "COM_10") (pintype "output"))
      (node (ref "V_VALVE") (pin "1") (pinfunction "1_1") (pintype "passive"))
    )
    (net (code "72") (name "Net-(U2-GND)") (class "Default")
      (node (ref "R16") (pin "2") (pinfunction "2_2") (pintype "passive"))
      (node (ref "U2") (pin "3") (pinfunction "GND_3") (pintype "power_in"))
      (node (ref "U4") (pin "2") (pinfunction "-IN_2") (pintype "input"))
    )
    (net (code "73") (name "Net-(U2-ICC)") (class "Default")
      (node (ref "J7") (pin "1") (pinfunction "1_1") (pintype "passive"))
      (node (ref "U2") (pin "6") (pinfunction "ICC_6") (pintype "input"))
      (node (ref "U4") (pin "1") (pinfunction "OUT_1") (pintype "output"))
    )
    (net (code "74") (name "Net-(U2-VOUT+)") (class "Default")
      (node (ref "U2") (pin "1") (pinfunction "VOUT+_1") (pintype "output"))
      (node (ref "U4") (pin "5") (pinfunction "+IN_5") (pintype "input"))
    )
    (net (code "75") (name "Net-(U2-VOUT-)") (class "Default")
      (node (ref "U2") (pin "4") (pinfunction "VOUT-_4") (pintype "output"))
      (node (ref "U4") (pin "10") (pinfunction "+IN_10") (pintype "input"))
    )
    (net (code "76") (name "Net-(U3A-+IN)") (class "Default")
      (node (ref "R22") (pin "1") (pinfunction "1_1") (pintype "passive"))
      (node (ref "R4") (pin "2") (pinfunction "2_2") (pintype "passive"))
      (node (ref "U3") (pin "3") (pinfunction "+IN_3") (pintype "input"))
    )
    (net (code "77") (name "Net-(U3B--IN)") (class "Default")
      (node (ref "R12") (pin "1") (pinfunction "1_1") (pintype "passive"))
      (node (ref "R3") (pin "1") (pinfunction "1_1") (pintype "passive"))
      (node (ref "U3") (pin "6") (pinfunction "-IN_6") (pintype "input"))
    )
    (net (code "78") (name "Net-(U3B-OUT)") (class "Default")
      (node (ref "J5") (pin "1") (pinfunction "1_1") (pintype "passive"))
      (node (ref "R12") (pin "2") (pinfunction "2_2") (pintype "passive"))
      (node (ref "R13") (pin "1") (pinfunction "1_1") (pintype "passive"))
      (node (ref "U3") (pin "7") (pinfunction "OUT_7") (pintype "output"))
    )
    (net (code "79") (name "Net-(U3C--IN)") (class "Default")
      (node (ref "R3") (pin "2") (pinfunction "2_2") (pintype "passive"))
      (node (ref "R9") (pin "1") (pinfunction "1_1") (pintype "passive"))
      (node (ref "U3") (pin "9") (pinfunction "-IN_9") (pintype "input"))
    )
    (net (code "80") (name "Net-(U3C-OUT)") (class "Default")
      (node (ref "J4") (pin "1") (pinfunction "1_1") (pintype "passive"))
      (node (ref "R10") (pin "2") (pinfunction "2_2") (pintype "passive"))
      (node (ref "R9") (pin "2") (pinfunction "2_2") (pintype "passive"))
      (node (ref "U3") (pin "8") (pinfunction "OUT_8") (pintype "output"))
    )
    (net (code "81") (name "Net-(U3D-+IN)") (class "Default")
      (node (ref "R13") (pin "2") (pinfunction "2_2") (pintype "passive"))
      (node (ref "R26") (pin "1") (pinfunction "1_1") (pintype "passive"))
      (node (ref "U3") (pin "12") (pinfunction "+IN_12") (pintype "input"))
    )
    (net (code "82") (name "Net-(U4B--IN)") (class "Default")
      (node (ref "R20") (pin "1") (pinfunction "1_1") (pintype "passive"))
      (node (ref "R21") (pin "1") (pinfunction "1_1") (pintype "passive"))
      (node (ref "U4") (pin "6") (pinfunction "-IN_6") (pintype "input"))
    )
    (net (code "83") (name "Net-(U4B-OUT)") (class "Default")
      (node (ref "J10") (pin "1") (pinfunction "1_1") (pintype "passive"))
      (node (ref "R21") (pin "2") (pinfunction "2_2") (pintype "passive"))
      (node (ref "R23") (pin "1") (pinfunction "1_1") (pintype "passive"))
      (node (ref "U4") (pin "7") (pinfunction "OUT_7") (pintype "output"))
    )
    (net (code "84") (name "Net-(U4C--IN)") (class "Default")
      (node (ref "R19") (pin "1") (pinfunction "1_1") (pintype "passive"))
      (node (ref "R20") (pin "2") (pinfunction "2_2") (pintype "passive"))
      (node (ref "U4") (pin "9") (pinfunction "-IN_9") (pintype "input"))
    )
    (net (code "85") (name "Net-(U4C-OUT)") (class "Default")
      (node (ref "J8") (pin "1") (pinfunction "1_1") (pintype "passive"))
      (node (ref "R17") (pin "2") (pinfunction "2_2") (pintype "passive"))
      (node (ref "R19") (pin "2") (pinfunction "2_2") (pintype "passive"))
      (node (ref "U4") (pin "8") (pinfunction "OUT_8") (pintype "output"))
    )
    (net (code "86") (name "Net-(U4D-+IN)") (class "Default")
      (node (ref "R23") (pin "2") (pinfunction "2_2") (pintype "passive"))
      (node (ref "R24") (pin "1") (pinfunction "1_1") (pintype "passive"))
      (node (ref "U4") (pin "12") (pinfunction "+IN_12") (pintype "input"))
    )
    (net (code "87") (name "Net-(U4D--IN)") (class "Default")
      (node (ref "R17") (pin "1") (pinfunction "1_1") (pintype "passive"))
      (node (ref "R18") (pin "2") (pinfunction "2_2") (pintype "passive"))
      (node (ref "U4") (pin "13") (pinfunction "-IN_13") (pintype "input"))
    )
    (net (code "88") (name "unconnected-(U1-N-SUB-Pad5)") (class "Default")
      (node (ref "U1") (pin "5") (pinfunction "N-SUB_5") (pintype "input"))
    )
    (net (code "89") (name "unconnected-(U2-N-SUB-Pad5)") (class "Default")
      (node (ref "U2") (pin "5") (pinfunction "N-SUB_5") (pintype "input"))
    )
    (net (code "90") (name "unconnected-(U3D--IN-Pad13)") (class "Default")
      (node (ref "U3") (pin "13") (pinfunction "-IN_13") (pintype "input"))
    )
    (net (code "91") (name "unconnected-(U4A-+IN-Pad3)") (class "Default")
      (node (ref "U4") (pin "3") (pinfunction "+IN_3") (pintype "input"))
    )
  )
)
